# cactar.net
KiCad netlist of a schematic drawn in EAGLE
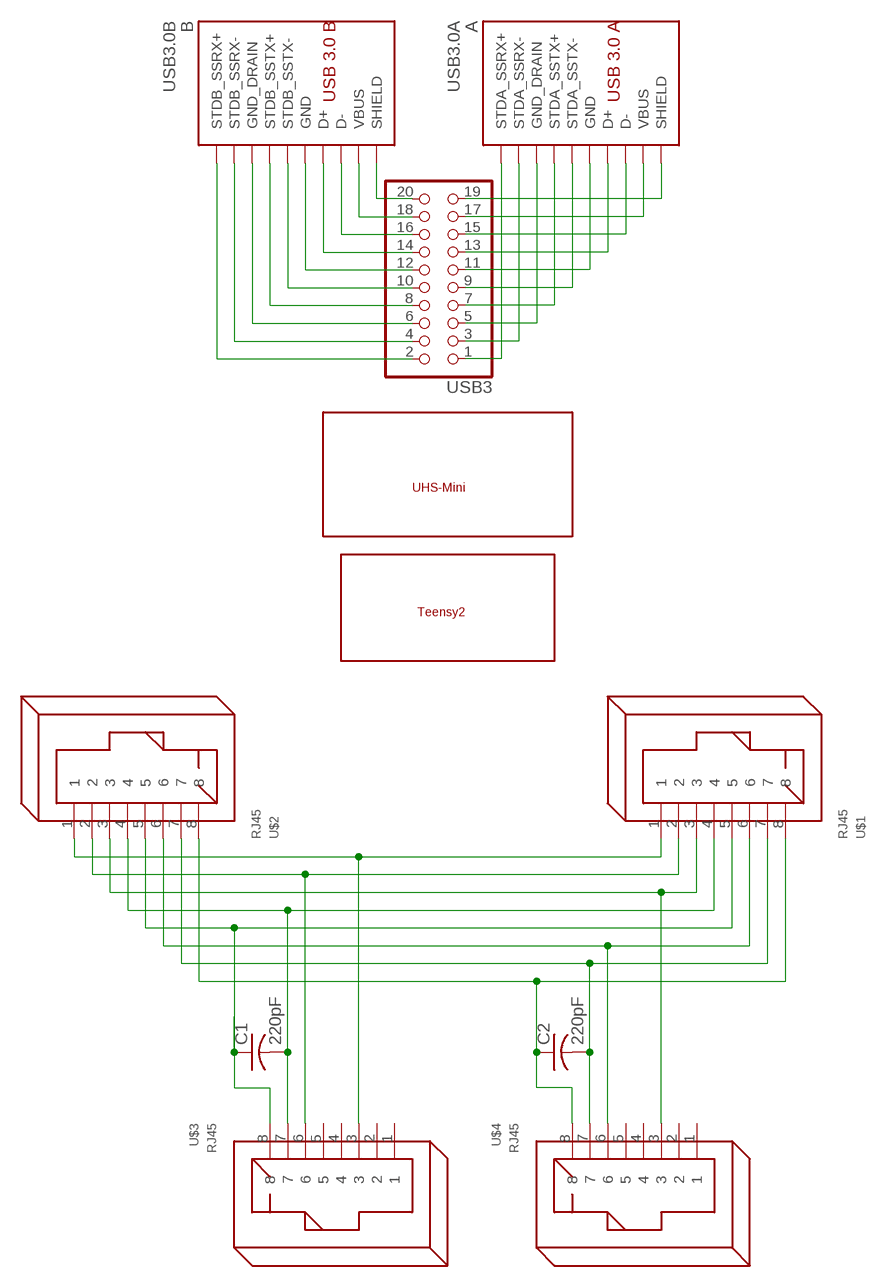
[diagram p0: schematic, sheet 1]

(export (version "E")
  (design (tool "Eeschema 10.0.6"))
  (components
    (comp (ref "A")
      (value "USB3.0A")
      (footprint "eagle-import:AMPHENOLUSB3.0A")
      (libsource (lib "eagle-import") (part "USB3.0A"))
    )
    (comp (ref "B")
      (value "USB3.0B")
      (footprint "eagle-import:AMPHENOLUSB3.0B")
      (libsource (lib "eagle-import") (part "USB3.0B"))
    )
    (comp (ref "C1")
      (value "220pF")
      (footprint "eagle-import:C050-025X075")
      (libsource (lib "eagle-import") (part "C-US050-025X075"))
    )
    (comp (ref "C2")
      (value "220pF")
      (footprint "eagle-import:C050-025X075")
      (libsource (lib "eagle-import") (part "C-US050-025X075"))
    )
    (comp (ref "U$1")
      (value "RJ45")
      (footprint "eagle-import:RJ45")
      (libsource (lib "eagle-import") (part "RJ45"))
    )
    (comp (ref "U$2")
      (value "RJ45")
      (footprint "eagle-import:RJ45")
      (libsource (lib "eagle-import") (part "RJ45"))
    )
    (comp (ref "U$3")
      (value "RJ45")
      (footprint "eagle-import:RJ45")
      (libsource (lib "eagle-import") (part "RJ45"))
    )
    (comp (ref "U$4")
      (value "RJ45")
      (footprint "eagle-import:RJ45")
      (libsource (lib "eagle-import") (part "RJ45"))
    )
    (comp (ref "U$5")
      (value "BREADLY")
      (footprint "eagle-import:BREADLY")
      (libsource (lib "eagle-import") (part "BREADLY"))
    )
    (comp (ref "USB3")
      (value "PINHD-2X102X10/MIRROR")
      (footprint "eagle-import:2X10_MIRROR")
      (libsource (lib "eagle-import") (part "PINHD-2X102X10/MIRROR"))
    )
    (comp (ref "_1")
      (value "TEENSY2")
      (footprint "eagle-import:TEENSY2")
      (libsource (lib "eagle-import") (part "TEENSY2"))
    )
  )
  (nets
    (net (code "1") (name "Net-(A-D+)") (class "Default")
      (node (ref "A") (pin "3") (pinfunction "D+_3") (pintype "bidirectional"))
      (node (ref "USB3") (pin "13") (pinfunction "13_13") (pintype "passive"))
    )
    (net (code "2") (name "Net-(A-D-)") (class "Default")
      (node (ref "A") (pin "2") (pinfunction "D-_2") (pintype "bidirectional"))
      (node (ref "USB3") (pin "15") (pinfunction "15_15") (pintype "passive"))
    )
    (net (code "3") (name "Net-(A-GND)") (class "Default")
      (node (ref "A") (pin "4") (pinfunction "GND_4") (pintype "bidirectional"))
      (node (ref "USB3") (pin "11") (pinfunction "11_11") (pintype "passive"))
    )
    (net (code "4") (name "Net-(A-GND_DRAIN)") (class "Default")
      (node (ref "A") (pin "7") (pinfunction "GND_DRAIN_7") (pintype "bidirectional"))
      (node (ref "USB3") (pin "5") (pinfunction "5_5") (pintype "passive"))
    )
    (net (code "5") (name "Net-(A-SHIELD-Pad10@1)") (class "Default")
      (node (ref "A") (pin "10@1") (pinfunction "SHIELD_10@1") (pintype "bidirectional"))
      (node (ref "A") (pin "10@2") (pinfunction "SHIELD_10@2") (pintype "bidirectional"))
      (node (ref "USB3") (pin "19") (pinfunction "19_19") (pintype "passive"))
    )
    (net (code "6") (name "Net-(A-STDA_SSRX+)") (class "Default")
      (node (ref "A") (pin "6") (pinfunction "STDA_SSRX+_6") (pintype "bidirectional"))
      (node (ref "USB3") (pin "1") (pinfunction "1_1") (pintype "passive"))
    )
    (net (code "7") (name "Net-(A-STDA_SSRX-)") (class "Default")
      (node (ref "A") (pin "5") (pinfunction "STDA_SSRX-_5") (pintype "bidirectional"))
      (node (ref "USB3") (pin "3") (pinfunction "3_3") (pintype "passive"))
    )
    (net (code "8") (name "Net-(A-STDA_SSTX+)") (class "Default")
      (node (ref "A") (pin "9") (pinfunction "STDA_SSTX+_9") (pintype "bidirectional"))
      (node (ref "USB3") (pin "7") (pinfunction "7_7") (pintype "passive"))
    )
    (net (code "9") (name "Net-(A-STDA_SSTX-)") (class "Default")
      (node (ref "A") (pin "8") (pinfunction "STDA_SSTX-_8") (pintype "bidirectional"))
      (node (ref "USB3") (pin "9") (pinfunction "9_9") (pintype "passive"))
    )
    (net (code "10") (name "Net-(A-VBUS)") (class "Default")
      (node (ref "A") (pin "1") (pinfunction "VBUS_1") (pintype "bidirectional"))
      (node (ref "USB3") (pin "17") (pinfunction "17_17") (pintype "passive"))
    )
    (net (code "11") (name "Net-(B-D+)") (class "Default")
      (node (ref "B") (pin "3") (pinfunction "D+_3") (pintype "bidirectional"))
      (node (ref "USB3") (pin "14") (pinfunction "14_14") (pintype "passive"))
    )
    (net (code "12") (name "Net-(B-D-)") (class "Default")
      (node (ref "B") (pin "2") (pinfunction "D-_2") (pintype "bidirectional"))
      (node (ref "USB3") (pin "16") (pinfunction "16_16") (pintype "passive"))
    )
    (net (code "13") (name "Net-(B-GND)") (class "Default")
      (node (ref "B") (pin "4") (pinfunction "GND_4") (pintype "bidirectional"))
      (node (ref "USB3") (pin "12") (pinfunction "12_12") (pintype "passive"))
    )
    (net (code "14") (name "Net-(B-GND_DRAIN)") (class "Default")
      (node (ref "B") (pin "7") (pinfunction "GND_DRAIN_7") (pintype "bidirectional"))
      (node (ref "USB3") (pin "6") (pinfunction "6_6") (pintype "passive"))
    )
    (net (code "15") (name "Net-(B-SHIELD-Pad10@1)") (class "Default")
      (node (ref "B") (pin "10@1") (pinfunction "SHIELD_10@1") (pintype "bidirectional"))
      (node (ref "B") (pin "10@2") (pinfunction "SHIELD_10@2") (pintype "bidirectional"))
      (node (ref "USB3") (pin "20") (pinfunction "20_20") (pintype "passive"))
    )
    (net (code "16") (name "Net-(B-STDB_SSRX+)") (class "Default")
      (node (ref "B") (pin "9") (pinfunction "STDB_SSRX+_9") (pintype "bidirectional"))
      (node (ref "USB3") (pin "2") (pinfunction "2_2") (pintype "passive"))
    )
    (net (code "17") (name "Net-(B-STDB_SSRX-)") (class "Default")
      (node (ref "B") (pin "8") (pinfunction "STDB_SSRX-_8") (pintype "bidirectional"))
      (node (ref "USB3") (pin "4") (pinfunction "4_4") (pintype "passive"))
    )
    (net (code "18") (name "Net-(B-STDB_SSTX+)") (class "Default")
      (node (ref "B") (pin "6") (pinfunction "STDB_SSTX+_6") (pintype "bidirectional"))
      (node (ref "USB3") (pin "8") (pinfunction "8_8") (pintype "passive"))
    )
    (net (code "19") (name "Net-(B-STDB_SSTX-)") (class "Default")
      (node (ref "B") (pin "5") (pinfunction "STDB_SSTX-_5") (pintype "bidirectional"))
      (node (ref "USB3") (pin "10") (pinfunction "10_10") (pintype "passive"))
    )
    (net (code "20") (name "Net-(B-VBUS)") (class "Default")
      (node (ref "B") (pin "1") (pinfunction "VBUS_1") (pintype "bidirectional"))
      (node (ref "USB3") (pin "18") (pinfunction "18_18") (pintype "passive"))
    )
    (net (code "21") (name "Net-(C1-Pad1)") (class "Default")
      (node (ref "C1") (pin "1") (pinfunction "1_1") (pintype "passive"))
      (node (ref "U$1") (pin "5") (pinfunction "5_5") (pintype "bidirectional"))
      (node (ref "U$2") (pin "5") (pinfunction "5_5") (pintype "bidirectional"))
      (node (ref "U$3") (pin "8") (pinfunction "8_8") (pintype "bidirectional"))
    )
    (net (code "22") (name "Net-(C1-Pad2)") (class "Default")
      (node (ref "C1") (pin "2") (pinfunction "2_2") (pintype "passive"))
      (node (ref "U$1") (pin "4") (pinfunction "4_4") (pintype "bidirectional"))
      (node (ref "U$2") (pin "4") (pinfunction "4_4") (pintype "bidirectional"))
      (node (ref "U$3") (pin "7") (pinfunction "7_7") (pintype "bidirectional"))
    )
    (net (code "23") (name "Net-(C2-Pad1)") (class "Default")
      (node (ref "C2") (pin "1") (pinfunction "1_1") (pintype "passive"))
      (node (ref "U$1") (pin "8") (pinfunction "8_8") (pintype "bidirectional"))
      (node (ref "U$2") (pin "8") (pinfunction "8_8") (pintype "bidirectional"))
      (node (ref "U$4") (pin "8") (pinfunction "8_8") (pintype "bidirectional"))
    )
    (net (code "24") (name "Net-(C2-Pad2)") (class "Default")
      (node (ref "C2") (pin "2") (pinfunction "2_2") (pintype "passive"))
      (node (ref "U$1") (pin "7") (pinfunction "7_7") (pintype "bidirectional"))
      (node (ref "U$2") (pin "7") (pinfunction "7_7") (pintype "bidirectional"))
      (node (ref "U$4") (pin "7") (pinfunction "7_7") (pintype "bidirectional"))
    )
    (net (code "25") (name "Net-(U$1-Pad1)") (class "Default")
      (node (ref "U$1") (pin "1") (pinfunction "1_1") (pintype "bidirectional"))
      (node (ref "U$2") (pin "1") (pinfunction "1_1") (pintype "bidirectional"))
      (node (ref "U$3") (pin "3") (pinfunction "3_3") (pintype "bidirectional"))
    )
    (net (code "26") (name "Net-(U$1-Pad2)") (class "Default")
      (node (ref "U$1") (pin "2") (pinfunction "2_2") (pintype "bidirectional"))
      (node (ref "U$2") (pin "2") (pinfunction "2_2") (pintype "bidirectional"))
      (node (ref "U$3") (pin "6") (pinfunction "6_6") (pintype "bidirectional"))
    )
    (net (code "27") (name "Net-(U$1-Pad3)") (class "Default")
      (node (ref "U$1") (pin "3") (pinfunction "3_3") (pintype "bidirectional"))
      (node (ref "U$2") (pin "3") (pinfunction "3_3") (pintype "bidirectional"))
      (node (ref "U$4") (pin "3") (pinfunction "3_3") (pintype "bidirectional"))
    )
    (net (code "28") (name "Net-(U$1-Pad6)") (class "Default")
      (node (ref "U$1") (pin "6") (pinfunction "6_6") (pintype "bidirectional"))
      (node (ref "U$2") (pin "6") (pinfunction "6_6") (pintype "bidirectional"))
      (node (ref "U$4") (pin "6") (pinfunction "6_6") (pintype "bidirectional"))
    )
    (net (code "29") (name "unconnected-(U$3-Pad1)") (class "Default")
      (node (ref "U$3") (pin "1") (pinfunction "1_1") (pintype "bidirectional"))
    )
    (net (code "30") (name "unconnected-(U$3-Pad2)") (class "Default")
      (node (ref "U$3") (pin "2") (pinfunction "2_2") (pintype "bidirectional"))
    )
    (net (code "31") (name "unconnected-(U$3-Pad4)") (class "Default")
      (node (ref "U$3") (pin "4") (pinfunction "4_4") (pintype "bidirectional"))
    )
    (net (code "32") (name "unconnected-(U$3-Pad5)") (class "Default")
      (node (ref "U$3") (pin "5") (pinfunction "5_5") (pintype "bidirectional"))
    )
    (net (code "33") (name "unconnected-(U$4-Pad1)") (class "Default")
      (node (ref "U$4") (pin "1") (pinfunction "1_1") (pintype "bidirectional"))
    )
    (net (code "34") (name "unconnected-(U$4-Pad2)") (class "Default")
      (node (ref "U$4") (pin "2") (pinfunction "2_2") (pintype "bidirectional"))
    )
    (net (code "35") (name "unconnected-(U$4-Pad4)") (class "Default")
      (node (ref "U$4") (pin "4") (pinfunction "4_4") (pintype "bidirectional"))
    )
    (net (code "36") (name "unconnected-(U$4-Pad5)") (class "Default")
      (node (ref "U$4") (pin "5") (pinfunction "5_5") (pintype "bidirectional"))
    )
  )
)
